# polosyzeros.net
KiCad netlist of a schematic drawn in Altium Designer
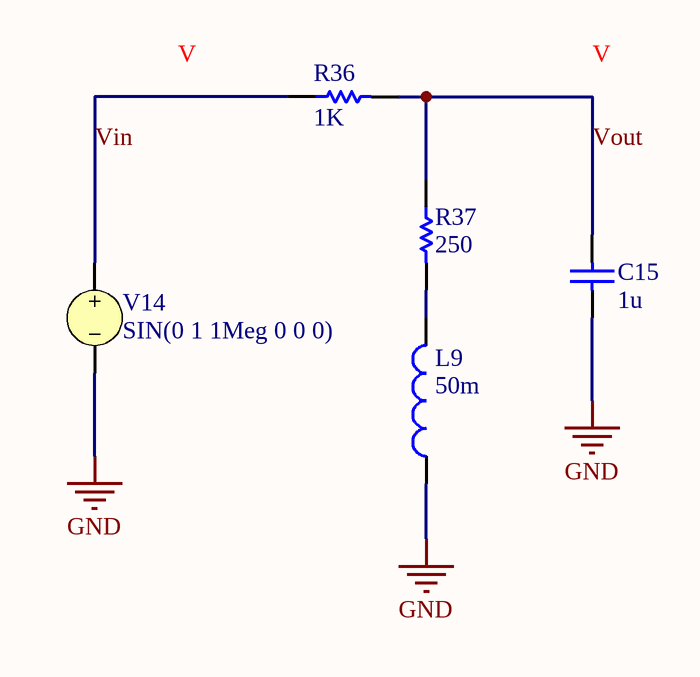
[diagram p0: polosyzeros.SchDoc]

(export (version "E")
  (design (tool "Eeschema 10.0.6"))
  (components
    (comp (ref "C15")
      (value "1u")
      (description "Capacitor")
      (libsource (lib "Simulation Generic Components") (part "Capacitor"))
    )
    (comp (ref "L9")
      (value "50m")
      (description "Inductor")
      (libsource (lib "Simulation Generic Components") (part "Inductor"))
    )
    (comp (ref "R36")
      (value "1K")
      (description "Resistor")
      (libsource (lib "Simulation Generic Components") (part "Resistor"))
    )
    (comp (ref "R37")
      (value "250")
      (description "Resistor")
      (libsource (lib "Simulation Generic Components") (part "Resistor"))
    )
    (comp (ref "V14")
      (value "SIN(0 1 1Meg 0 0 0)")
      (description "Voltage Source")
      (fields (field (name "PUBLISHER") "Altium Limited"))
      (libsource (lib "Simulation Generic Components") (part "VSRC"))
    )
  )
  (nets
    (net (code "1") (name "/Vin") (class "Default")
      (node (ref "R36") (pin "1") (pinfunction "1_1") (pintype "passive"))
      (node (ref "V14") (pin "1") (pinfunction "1_1") (pintype "passive"))
    )
    (net (code "2") (name "/Vout") (class "Default")
      (node (ref "C15") (pin "2") (pinfunction "2_2") (pintype "passive"))
      (node (ref "R36") (pin "2") (pinfunction "2_2") (pintype "passive"))
      (node (ref "R37") (pin "1") (pinfunction "1_1") (pintype "passive"))
    )
    (net (code "3") (name "GND") (class "Default")
      (node (ref "C15") (pin "1") (pinfunction "1_1") (pintype "passive"))
      (node (ref "L9") (pin "1") (pinfunction "1_1") (pintype "passive"))
      (node (ref "V14") (pin "2") (pinfunction "2_2") (pintype "passive"))
    )
    (net (code "4") (name "Net-(L9-Pad2)") (class "Default")
      (node (ref "L9") (pin "2") (pinfunction "2_2") (pintype "passive"))
      (node (ref "R37") (pin "2") (pinfunction "2_2") (pintype "passive"))
    )
  )
)
